# calculator5.net
KiCad netlist of a schematic drawn in EAGLE
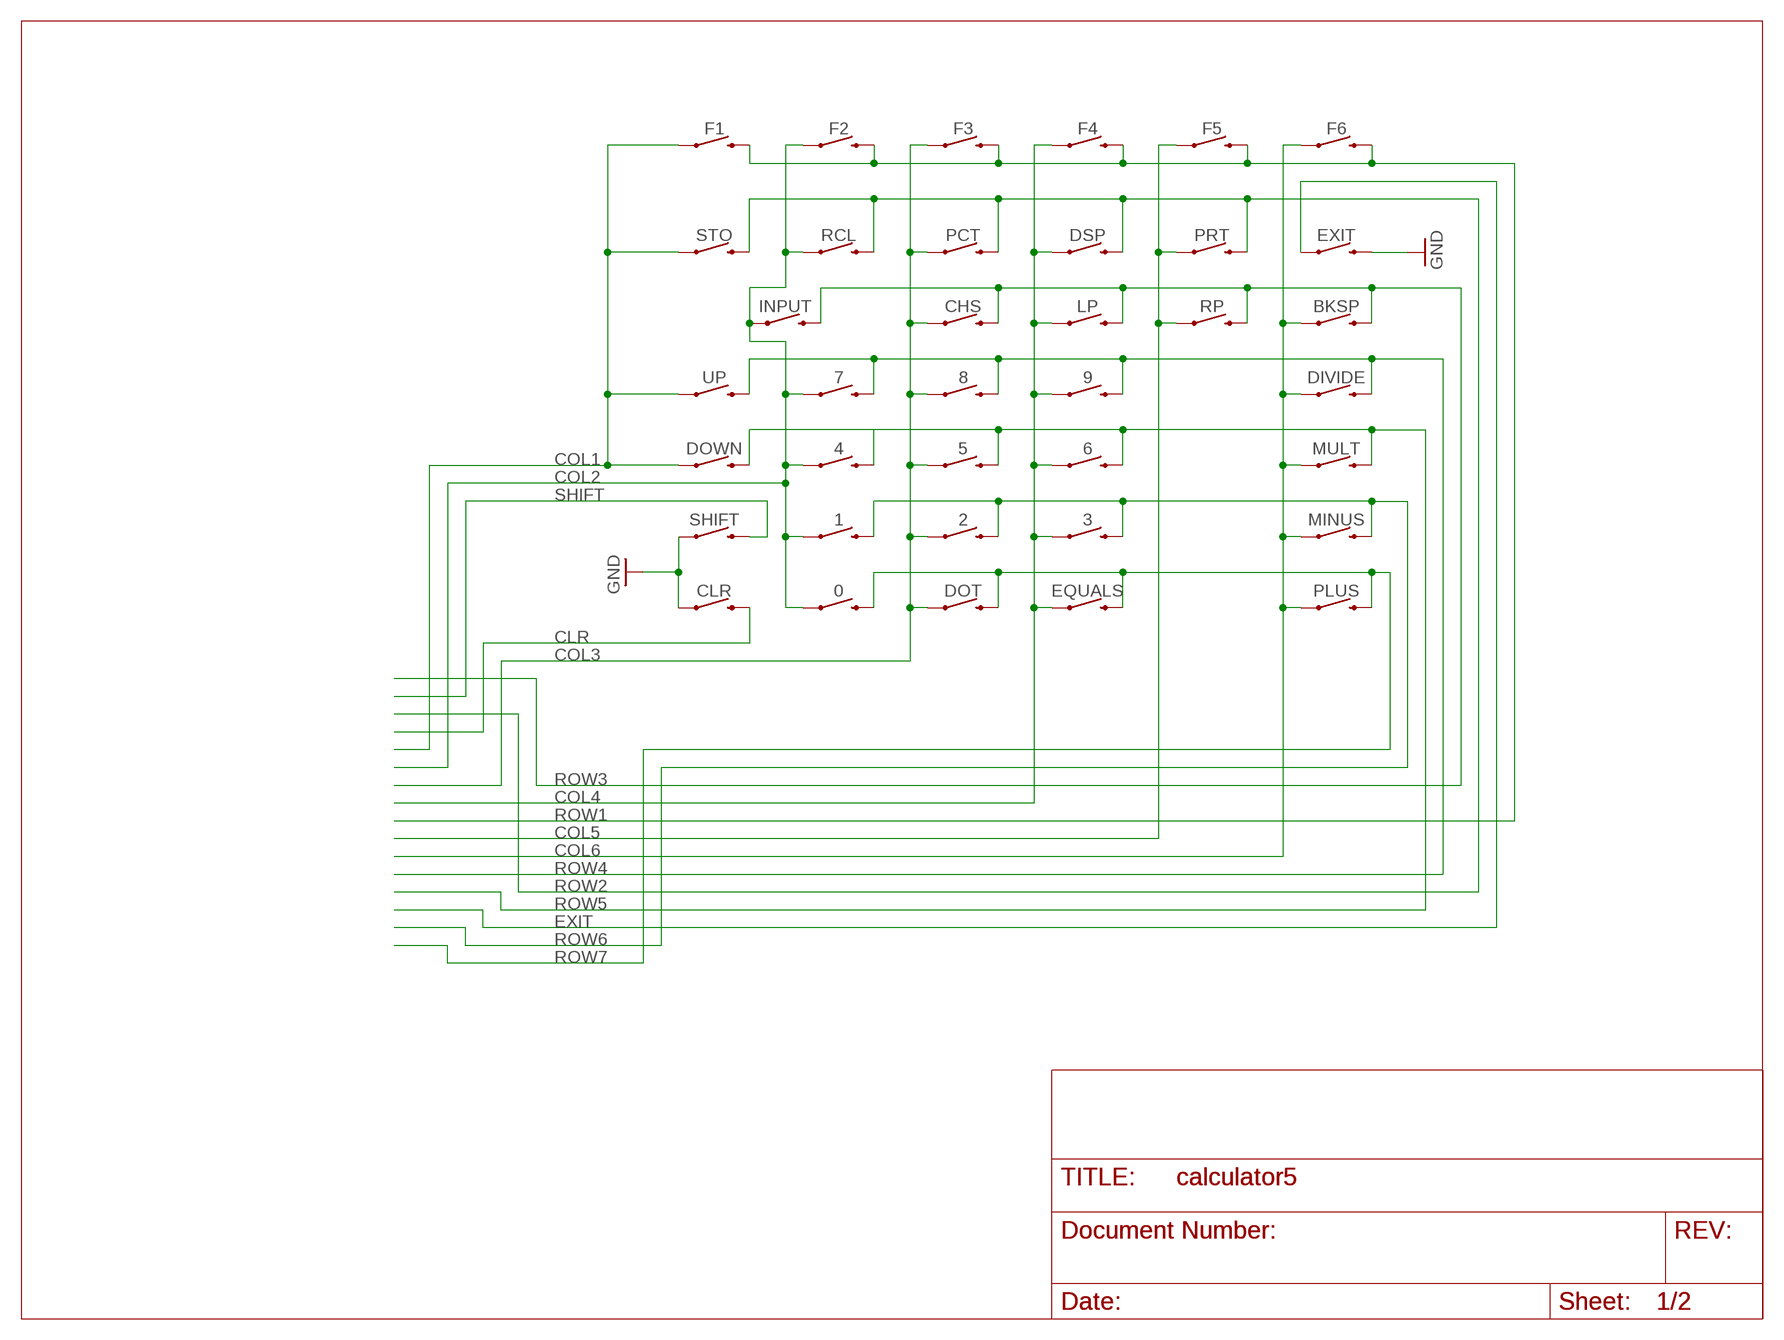
[diagram p0: schematic, sheet 1]
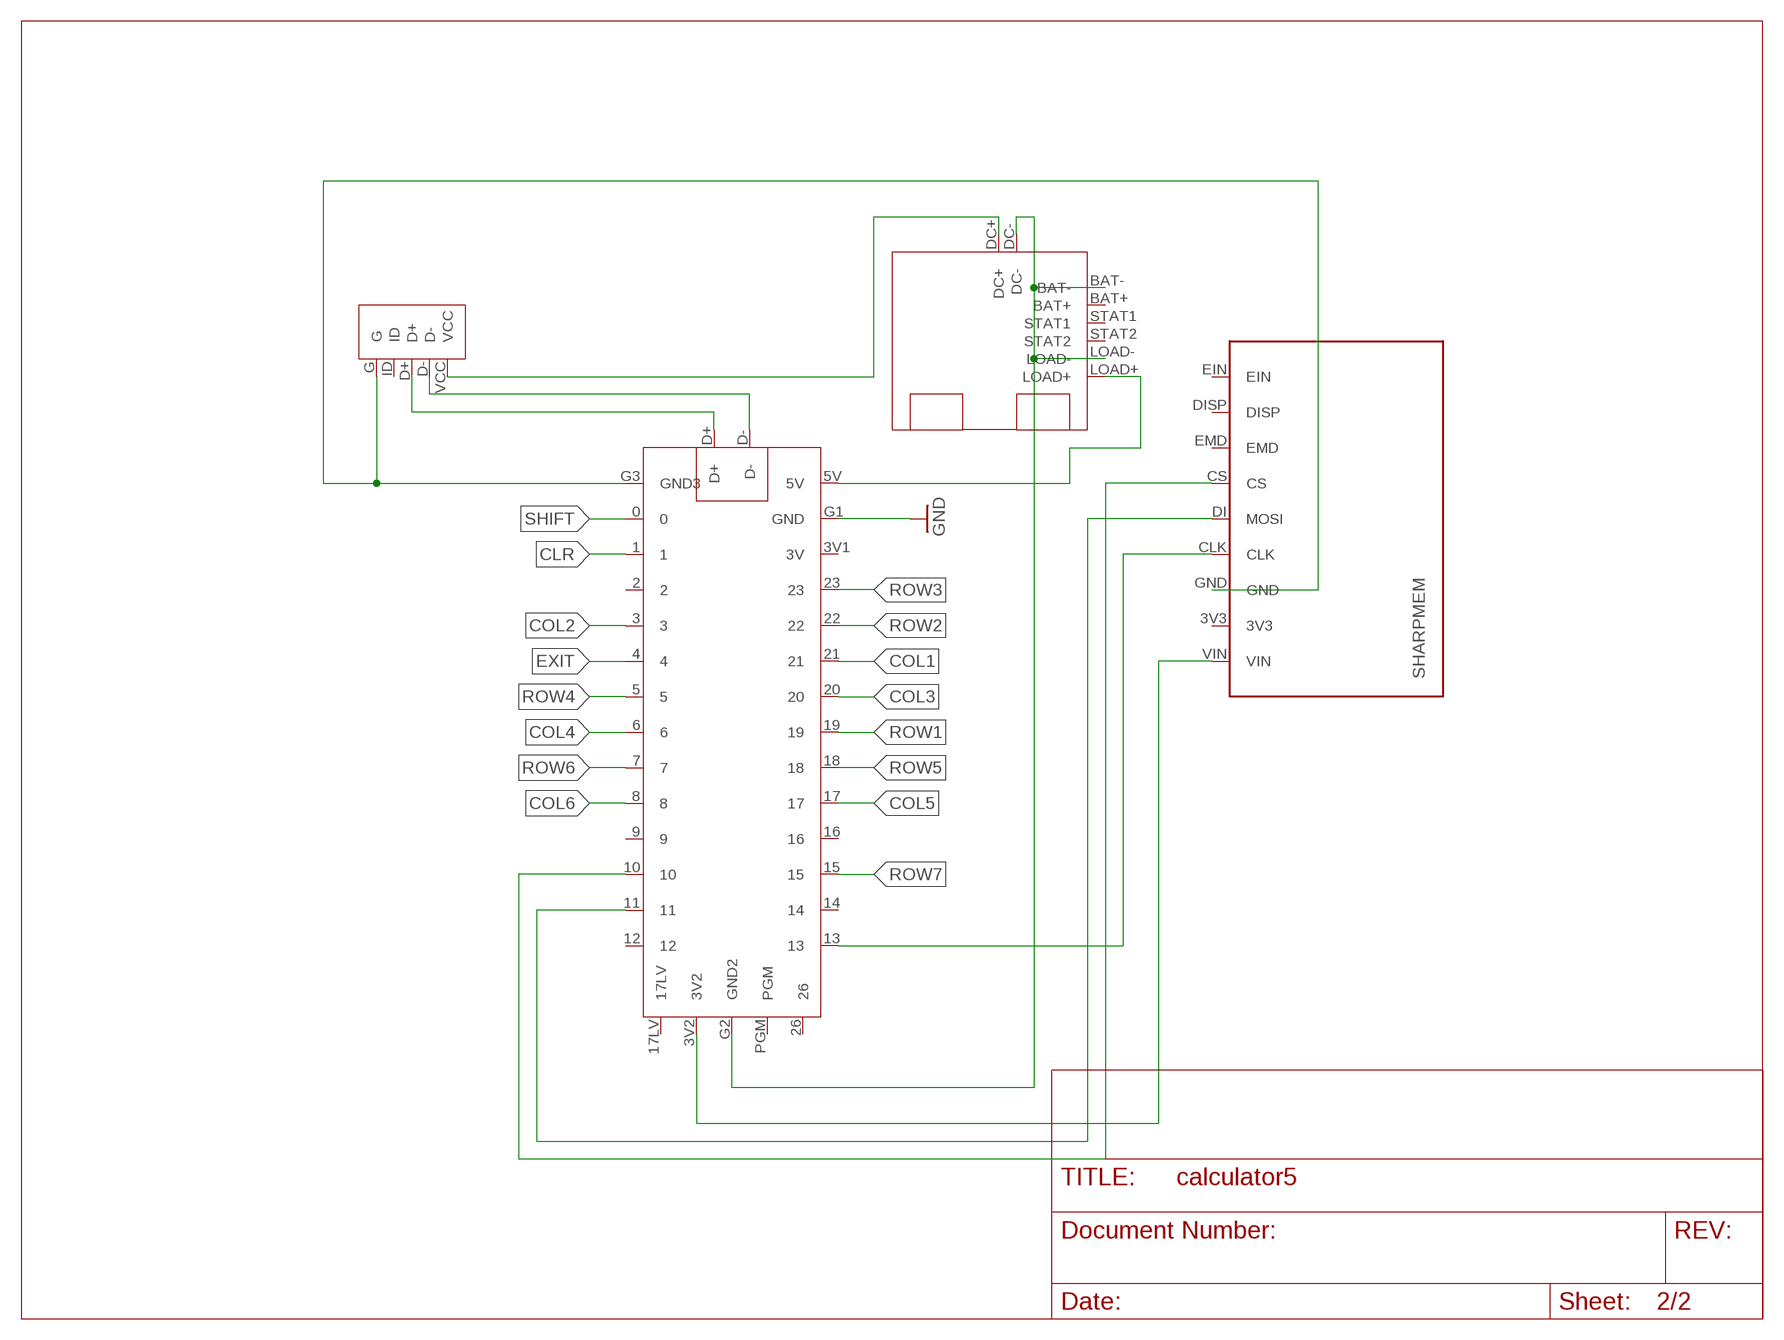
[diagram p1: schematic, sheet 2]

(export (version "E")
  (design (tool "Eeschema 10.0.6"))
  (components
    (comp (ref "0")
      (value "BUTTON")
      (footprint "eagle-import:BUTTON")
      (libsource (lib "eagle-import") (part "BUTTON"))
    )
    (comp (ref "1")
      (value "BUTTON")
      (footprint "eagle-import:BUTTON")
      (libsource (lib "eagle-import") (part "BUTTON"))
    )
    (comp (ref "2")
      (value "BUTTON")
      (footprint "eagle-import:BUTTON")
      (libsource (lib "eagle-import") (part "BUTTON"))
    )
    (comp (ref "3")
      (value "BUTTON")
      (footprint "eagle-import:BUTTON")
      (libsource (lib "eagle-import") (part "BUTTON"))
    )
    (comp (ref "4")
      (value "BUTTON")
      (footprint "eagle-import:BUTTON")
      (libsource (lib "eagle-import") (part "BUTTON"))
    )
    (comp (ref "5")
      (value "BUTTON")
      (footprint "eagle-import:BUTTON")
      (libsource (lib "eagle-import") (part "BUTTON"))
    )
    (comp (ref "6")
      (value "BUTTON")
      (footprint "eagle-import:BUTTON")
      (libsource (lib "eagle-import") (part "BUTTON"))
    )
    (comp (ref "7")
      (value "BUTTON")
      (footprint "eagle-import:BUTTON")
      (libsource (lib "eagle-import") (part "BUTTON"))
    )
    (comp (ref "8")
      (value "BUTTON")
      (footprint "eagle-import:BUTTON")
      (libsource (lib "eagle-import") (part "BUTTON"))
    )
    (comp (ref "9")
      (value "BUTTON")
      (footprint "eagle-import:BUTTON")
      (libsource (lib "eagle-import") (part "BUTTON"))
    )
    (comp (ref "BKSP")
      (value "BUTTON")
      (footprint "eagle-import:BUTTON")
      (libsource (lib "eagle-import") (part "BUTTON"))
    )
    (comp (ref "CHS")
      (value "BUTTON")
      (footprint "eagle-import:BUTTON")
      (libsource (lib "eagle-import") (part "BUTTON"))
    )
    (comp (ref "CLR")
      (value "BUTTON")
      (footprint "eagle-import:BUTTON")
      (libsource (lib "eagle-import") (part "BUTTON"))
    )
    (comp (ref "DIVIDE")
      (value "BUTTON")
      (footprint "eagle-import:BUTTON")
      (libsource (lib "eagle-import") (part "BUTTON"))
    )
    (comp (ref "DOT")
      (value "BUTTON")
      (footprint "eagle-import:BUTTON")
      (libsource (lib "eagle-import") (part "BUTTON"))
    )
    (comp (ref "DOWN")
      (value "BUTTON")
      (footprint "eagle-import:BUTTON")
      (libsource (lib "eagle-import") (part "BUTTON"))
    )
    (comp (ref "DSP")
      (value "BUTTON")
      (footprint "eagle-import:BUTTON")
      (libsource (lib "eagle-import") (part "BUTTON"))
    )
    (comp (ref "EQUALS")
      (value "BUTTON")
      (footprint "eagle-import:BUTTON")
      (libsource (lib "eagle-import") (part "BUTTON"))
    )
    (comp (ref "EXIT")
      (value "BUTTON")
      (footprint "eagle-import:BUTTON")
      (libsource (lib "eagle-import") (part "BUTTON"))
    )
    (comp (ref "F1")
      (value "BUTTON")
      (footprint "eagle-import:BUTTON")
      (libsource (lib "eagle-import") (part "BUTTON"))
    )
    (comp (ref "F2")
      (value "BUTTON")
      (footprint "eagle-import:BUTTON")
      (libsource (lib "eagle-import") (part "BUTTON"))
    )
    (comp (ref "F3")
      (value "BUTTON")
      (footprint "eagle-import:BUTTON")
      (libsource (lib "eagle-import") (part "BUTTON"))
    )
    (comp (ref "F4")
      (value "BUTTON")
      (footprint "eagle-import:BUTTON")
      (libsource (lib "eagle-import") (part "BUTTON"))
    )
    (comp (ref "F5")
      (value "BUTTON")
      (footprint "eagle-import:BUTTON")
      (libsource (lib "eagle-import") (part "BUTTON"))
    )
    (comp (ref "F6")
      (value "BUTTON")
      (footprint "eagle-import:BUTTON")
      (libsource (lib "eagle-import") (part "BUTTON"))
    )
    (comp (ref "INPUT")
      (value "BUTTON")
      (footprint "eagle-import:BUTTON")
      (libsource (lib "eagle-import") (part "BUTTON"))
    )
    (comp (ref "LP")
      (value "BUTTON")
      (footprint "eagle-import:BUTTON")
      (libsource (lib "eagle-import") (part "BUTTON"))
    )
    (comp (ref "MINUS")
      (value "BUTTON")
      (footprint "eagle-import:BUTTON")
      (libsource (lib "eagle-import") (part "BUTTON"))
    )
    (comp (ref "MULT")
      (value "BUTTON")
      (footprint "eagle-import:BUTTON")
      (libsource (lib "eagle-import") (part "BUTTON"))
    )
    (comp (ref "PCT")
      (value "BUTTON")
      (footprint "eagle-import:BUTTON")
      (libsource (lib "eagle-import") (part "BUTTON"))
    )
    (comp (ref "PLUS")
      (value "BUTTON")
      (footprint "eagle-import:BUTTON")
      (libsource (lib "eagle-import") (part "BUTTON"))
    )
    (comp (ref "PRT")
      (value "BUTTON")
      (footprint "eagle-import:BUTTON")
      (libsource (lib "eagle-import") (part "BUTTON"))
    )
    (comp (ref "RCL")
      (value "BUTTON")
      (footprint "eagle-import:BUTTON")
      (libsource (lib "eagle-import") (part "BUTTON"))
    )
    (comp (ref "RP")
      (value "BUTTON")
      (footprint "eagle-import:BUTTON")
      (libsource (lib "eagle-import") (part "BUTTON"))
    )
    (comp (ref "SHIFT")
      (value "BUTTON")
      (footprint "eagle-import:BUTTON")
      (libsource (lib "eagle-import") (part "BUTTON"))
    )
    (comp (ref "STO")
      (value "BUTTON")
      (footprint "eagle-import:BUTTON")
      (libsource (lib "eagle-import") (part "BUTTON"))
    )
    (comp (ref "UP")
      (value "BUTTON")
      (footprint "eagle-import:BUTTON")
      (libsource (lib "eagle-import") (part "BUTTON"))
    )
    (comp (ref "SHARPMEM")
      (value "SHARPMEM")
      (footprint "eagle-import:SHARPMEM")
      (libsource (lib "eagle-import") (part "SHARPMEM"))
    )
    (comp (ref "U$1")
      (value "TEENSY_LC")
      (footprint "eagle-import:TEENSY_LC")
      (libsource (lib "eagle-import") (part "TEENSY_LC"))
    )
    (comp (ref "U$2")
      (value "USB")
      (footprint "eagle-import:USB")
      (libsource (lib "eagle-import") (part "USB"))
    )
    (comp (ref "U$3")
      (value "LIPO_CHARGER")
      (footprint "eagle-import:LIPO_CHARGER")
      (libsource (lib "eagle-import") (part "LIPO_CHARGER"))
    )
  )
  (nets
    (net (code "1") (name "CLR") (class "Default")
      (node (ref "CLR") (pin "3") (pinfunction "2_3") (pintype "passive"))
      (node (ref "U$1") (pin "1") (pinfunction "1_1") (pintype "bidirectional"))
    )
    (net (code "2") (name "COL1") (class "Default")
      (node (ref "DOWN") (pin "1") (pinfunction "1_1") (pintype "passive"))
      (node (ref "F1") (pin "1") (pinfunction "1_1") (pintype "passive"))
      (node (ref "STO") (pin "1") (pinfunction "1_1") (pintype "passive"))
      (node (ref "U$1") (pin "21") (pinfunction "21_21") (pintype "bidirectional"))
      (node (ref "UP") (pin "1") (pinfunction "1_1") (pintype "passive"))
    )
    (net (code "3") (name "COL2") (class "Default")
      (node (ref "0") (pin "1") (pinfunction "1_1") (pintype "passive"))
      (node (ref "1") (pin "1") (pinfunction "1_1") (pintype "passive"))
      (node (ref "4") (pin "1") (pinfunction "1_1") (pintype "passive"))
      (node (ref "7") (pin "1") (pinfunction "1_1") (pintype "passive"))
      (node (ref "F2") (pin "1") (pinfunction "1_1") (pintype "passive"))
      (node (ref "INPUT") (pin "1") (pinfunction "1_1") (pintype "passive"))
      (node (ref "RCL") (pin "1") (pinfunction "1_1") (pintype "passive"))
      (node (ref "U$1") (pin "3") (pinfunction "3_3") (pintype "bidirectional"))
    )
    (net (code "4") (name "COL3") (class "Default")
      (node (ref "2") (pin "1") (pinfunction "1_1") (pintype "passive"))
      (node (ref "5") (pin "1") (pinfunction "1_1") (pintype "passive"))
      (node (ref "8") (pin "1") (pinfunction "1_1") (pintype "passive"))
      (node (ref "CHS") (pin "1") (pinfunction "1_1") (pintype "passive"))
      (node (ref "DOT") (pin "1") (pinfunction "1_1") (pintype "passive"))
      (node (ref "F3") (pin "1") (pinfunction "1_1") (pintype "passive"))
      (node (ref "PCT") (pin "1") (pinfunction "1_1") (pintype "passive"))
      (node (ref "U$1") (pin "20") (pinfunction "20_20") (pintype "bidirectional"))
    )
    (net (code "5") (name "COL4") (class "Default")
      (node (ref "3") (pin "1") (pinfunction "1_1") (pintype "passive"))
      (node (ref "6") (pin "1") (pinfunction "1_1") (pintype "passive"))
      (node (ref "9") (pin "1") (pinfunction "1_1") (pintype "passive"))
      (node (ref "DSP") (pin "1") (pinfunction "1_1") (pintype "passive"))
      (node (ref "EQUALS") (pin "1") (pinfunction "1_1") (pintype "passive"))
      (node (ref "F4") (pin "1") (pinfunction "1_1") (pintype "passive"))
      (node (ref "LP") (pin "1") (pinfunction "1_1") (pintype "passive"))
      (node (ref "U$1") (pin "6") (pinfunction "6_6") (pintype "bidirectional"))
    )
    (net (code "6") (name "COL5") (class "Default")
      (node (ref "F5") (pin "1") (pinfunction "1_1") (pintype "passive"))
      (node (ref "PRT") (pin "1") (pinfunction "1_1") (pintype "passive"))
      (node (ref "RP") (pin "1") (pinfunction "1_1") (pintype "passive"))
      (node (ref "U$1") (pin "17") (pinfunction "17_17") (pintype "bidirectional"))
    )
    (net (code "7") (name "COL6") (class "Default")
      (node (ref "BKSP") (pin "1") (pinfunction "1_1") (pintype "passive"))
      (node (ref "DIVIDE") (pin "1") (pinfunction "1_1") (pintype "passive"))
      (node (ref "F6") (pin "1") (pinfunction "1_1") (pintype "passive"))
      (node (ref "MINUS") (pin "1") (pinfunction "1_1") (pintype "passive"))
      (node (ref "MULT") (pin "1") (pinfunction "1_1") (pintype "passive"))
      (node (ref "PLUS") (pin "1") (pinfunction "1_1") (pintype "passive"))
      (node (ref "U$1") (pin "8") (pinfunction "8_8") (pintype "bidirectional"))
    )
    (net (code "8") (name "EXIT") (class "Default")
      (node (ref "EXIT") (pin "1") (pinfunction "1_1") (pintype "passive"))
      (node (ref "U$1") (pin "4") (pinfunction "4_4") (pintype "bidirectional"))
    )
    (net (code "9") (name "GND") (class "Default")
      (node (ref "CLR") (pin "1") (pinfunction "1_1") (pintype "passive"))
      (node (ref "EXIT") (pin "3") (pinfunction "2_3") (pintype "passive"))
      (node (ref "SHIFT") (pin "1") (pinfunction "1_1") (pintype "passive"))
      (node (ref "U$1") (pin "G1") (pinfunction "GND_G1") (pintype "bidirectional"))
    )
    (net (code "10") (name "Net-(SHARPMEM-MOSI)") (class "Default")
      (node (ref "SHARPMEM") (pin "DI") (pinfunction "MOSI_DI") (pintype "bidirectional"))
      (node (ref "U$1") (pin "11") (pinfunction "11_11") (pintype "bidirectional"))
    )
    (net (code "11") (name "Net-(SHARPMEM-PadCLK)") (class "Default")
      (node (ref "SHARPMEM") (pin "CLK") (pinfunction "CLK_CLK") (pintype "bidirectional"))
      (node (ref "U$1") (pin "13") (pinfunction "13_13") (pintype "bidirectional"))
    )
    (net (code "12") (name "Net-(SHARPMEM-PadCS)") (class "Default")
      (node (ref "SHARPMEM") (pin "CS") (pinfunction "CS_CS") (pintype "bidirectional"))
      (node (ref "U$1") (pin "10") (pinfunction "10_10") (pintype "bidirectional"))
    )
    (net (code "13") (name "Net-(SHARPMEM-PadVIN)") (class "Default")
      (node (ref "SHARPMEM") (pin "VIN") (pinfunction "VIN_VIN") (pintype "bidirectional"))
      (node (ref "U$1") (pin "3V2") (pinfunction "3V2_3V2") (pintype "bidirectional"))
    )
    (net (code "14") (name "Net-(U$1-GND2)") (class "Default")
      (node (ref "U$1") (pin "G2") (pinfunction "GND2_G2") (pintype "bidirectional"))
      (node (ref "U$3") (pin "BAT-") (pinfunction "BAT-_BAT-") (pintype "bidirectional"))
      (node (ref "U$3") (pin "DC-") (pinfunction "DC-_DC-") (pintype "bidirectional"))
      (node (ref "U$3") (pin "LOAD-") (pinfunction "LOAD-_LOAD-") (pintype "bidirectional"))
    )
    (net (code "15") (name "Net-(U$1-GND3)") (class "Default")
      (node (ref "SHARPMEM") (pin "GND") (pinfunction "GND_GND") (pintype "bidirectional"))
      (node (ref "U$1") (pin "G3") (pinfunction "GND3_G3") (pintype "bidirectional"))
      (node (ref "U$2") (pin "G") (pinfunction "G_G") (pintype "bidirectional"))
    )
    (net (code "16") (name "Net-(U$1-Pad5V)") (class "Default")
      (node (ref "U$1") (pin "5V") (pinfunction "5V_5V") (pintype "bidirectional"))
      (node (ref "U$3") (pin "LOAD+") (pinfunction "LOAD+_LOAD+") (pintype "bidirectional"))
    )
    (net (code "17") (name "Net-(U$1-PadD+)") (class "Default")
      (node (ref "U$1") (pin "D+") (pinfunction "D+_D+") (pintype "bidirectional"))
      (node (ref "U$2") (pin "D+") (pinfunction "D+_D+") (pintype "bidirectional"))
    )
    (net (code "18") (name "Net-(U$1-PadD-)") (class "Default")
      (node (ref "U$1") (pin "D-") (pinfunction "D-_D-") (pintype "bidirectional"))
      (node (ref "U$2") (pin "D-") (pinfunction "D-_D-") (pintype "bidirectional"))
    )
    (net (code "19") (name "Net-(U$2-PadVCC)") (class "Default")
      (node (ref "U$2") (pin "VCC") (pinfunction "VCC_VCC") (pintype "bidirectional"))
      (node (ref "U$3") (pin "DC+") (pinfunction "DC+_DC+") (pintype "bidirectional"))
    )
    (net (code "20") (name "ROW1") (class "Default")
      (node (ref "F1") (pin "3") (pinfunction "2_3") (pintype "passive"))
      (node (ref "F2") (pin "3") (pinfunction "2_3") (pintype "passive"))
      (node (ref "F3") (pin "3") (pinfunction "2_3") (pintype "passive"))
      (node (ref "F4") (pin "3") (pinfunction "2_3") (pintype "passive"))
      (node (ref "F5") (pin "3") (pinfunction "2_3") (pintype "passive"))
      (node (ref "F6") (pin "3") (pinfunction "2_3") (pintype "passive"))
      (node (ref "U$1") (pin "19") (pinfunction "19_19") (pintype "bidirectional"))
    )
    (net (code "21") (name "ROW2") (class "Default")
      (node (ref "DSP") (pin "3") (pinfunction "2_3") (pintype "passive"))
      (node (ref "PCT") (pin "3") (pinfunction "2_3") (pintype "passive"))
      (node (ref "PRT") (pin "3") (pinfunction "2_3") (pintype "passive"))
      (node (ref "RCL") (pin "3") (pinfunction "2_3") (pintype "passive"))
      (node (ref "STO") (pin "3") (pinfunction "2_3") (pintype "passive"))
      (node (ref "U$1") (pin "22") (pinfunction "22_22") (pintype "bidirectional"))
    )
    (net (code "22") (name "ROW3") (class "Default")
      (node (ref "BKSP") (pin "3") (pinfunction "2_3") (pintype "passive"))
      (node (ref "CHS") (pin "3") (pinfunction "2_3") (pintype "passive"))
      (node (ref "INPUT") (pin "3") (pinfunction "2_3") (pintype "passive"))
      (node (ref "LP") (pin "3") (pinfunction "2_3") (pintype "passive"))
      (node (ref "RP") (pin "3") (pinfunction "2_3") (pintype "passive"))
      (node (ref "U$1") (pin "23") (pinfunction "23_23") (pintype "bidirectional"))
    )
    (net (code "23") (name "ROW4") (class "Default")
      (node (ref "7") (pin "3") (pinfunction "2_3") (pintype "passive"))
      (node (ref "8") (pin "3") (pinfunction "2_3") (pintype "passive"))
      (node (ref "9") (pin "3") (pinfunction "2_3") (pintype "passive"))
      (node (ref "DIVIDE") (pin "3") (pinfunction "2_3") (pintype "passive"))
      (node (ref "U$1") (pin "5") (pinfunction "5_5") (pintype "bidirectional"))
      (node (ref "UP") (pin "3") (pinfunction "2_3") (pintype "passive"))
    )
    (net (code "24") (name "ROW5") (class "Default")
      (node (ref "4") (pin "3") (pinfunction "2_3") (pintype "passive"))
      (node (ref "5") (pin "3") (pinfunction "2_3") (pintype "passive"))
      (node (ref "6") (pin "3") (pinfunction "2_3") (pintype "passive"))
      (node (ref "DOWN") (pin "3") (pinfunction "2_3") (pintype "passive"))
      (node (ref "MULT") (pin "3") (pinfunction "2_3") (pintype "passive"))
      (node (ref "U$1") (pin "18") (pinfunction "18_18") (pintype "bidirectional"))
    )
    (net (code "25") (name "ROW6") (class "Default")
      (node (ref "1") (pin "3") (pinfunction "2_3") (pintype "passive"))
      (node (ref "2") (pin "3") (pinfunction "2_3") (pintype "passive"))
      (node (ref "3") (pin "3") (pinfunction "2_3") (pintype "passive"))
      (node (ref "MINUS") (pin "3") (pinfunction "2_3") (pintype "passive"))
      (node (ref "U$1") (pin "7") (pinfunction "7_7") (pintype "bidirectional"))
    )
    (net (code "26") (name "ROW7") (class "Default")
      (node (ref "0") (pin "3") (pinfunction "2_3") (pintype "passive"))
      (node (ref "DOT") (pin "3") (pinfunction "2_3") (pintype "passive"))
      (node (ref "EQUALS") (pin "3") (pinfunction "2_3") (pintype "passive"))
      (node (ref "PLUS") (pin "3") (pinfunction "2_3") (pintype "passive"))
      (node (ref "U$1") (pin "15") (pinfunction "15_15") (pintype "bidirectional"))
    )
    (net (code "27") (name "SHIFT") (class "Default")
      (node (ref "SHIFT") (pin "3") (pinfunction "2_3") (pintype "passive"))
      (node (ref "U$1") (pin "0") (pinfunction "0_0") (pintype "bidirectional"))
    )
    (net (code "28") (name "unconnected-(SHARPMEM-Pad3V3)") (class "Default")
      (node (ref "SHARPMEM") (pin "3V3") (pinfunction "3V3_3V3") (pintype "bidirectional"))
    )
    (net (code "29") (name "unconnected-(SHARPMEM-PadDISP)") (class "Default")
      (node (ref "SHARPMEM") (pin "DISP") (pinfunction "DISP_DISP") (pintype "bidirectional"))
    )
    (net (code "30") (name "unconnected-(SHARPMEM-PadEIN)") (class "Default")
      (node (ref "SHARPMEM") (pin "EIN") (pinfunction "EIN_EIN") (pintype "bidirectional"))
    )
    (net (code "31") (name "unconnected-(SHARPMEM-PadEMD)") (class "Default")
      (node (ref "SHARPMEM") (pin "EMD") (pinfunction "EMD_EMD") (pintype "bidirectional"))
    )
    (net (code "32") (name "unconnected-(U$1-3V-Pad3V1)") (class "Default")
      (node (ref "U$1") (pin "3V1") (pinfunction "3V_3V1") (pintype "bidirectional"))
    )
    (net (code "33") (name "unconnected-(U$1-Pad2)") (class "Default")
      (node (ref "U$1") (pin "2") (pinfunction "2_2") (pintype "bidirectional"))
    )
    (net (code "34") (name "unconnected-(U$1-Pad9)") (class "Default")
      (node (ref "U$1") (pin "9") (pinfunction "9_9") (pintype "bidirectional"))
    )
    (net (code "35") (name "unconnected-(U$1-Pad12)") (class "Default")
      (node (ref "U$1") (pin "12") (pinfunction "12_12") (pintype "bidirectional"))
    )
    (net (code "36") (name "unconnected-(U$1-Pad14)") (class "Default")
      (node (ref "U$1") (pin "14") (pinfunction "14_14") (pintype "bidirectional"))
    )
    (net (code "37") (name "unconnected-(U$1-Pad16)") (class "Default")
      (node (ref "U$1") (pin "16") (pinfunction "16_16") (pintype "bidirectional"))
    )
    (net (code "38") (name "unconnected-(U$1-Pad17LV)") (class "Default")
      (node (ref "U$1") (pin "17LV") (pinfunction "17LV_17LV") (pintype "bidirectional"))
    )
    (net (code "39") (name "unconnected-(U$1-Pad26)") (class "Default")
      (node (ref "U$1") (pin "26") (pinfunction "26_26") (pintype "bidirectional"))
    )
    (net (code "40") (name "unconnected-(U$1-PadPGM)") (class "Default")
      (node (ref "U$1") (pin "PGM") (pinfunction "PGM_PGM") (pintype "bidirectional"))
    )
    (net (code "41") (name "unconnected-(U$2-PadID)") (class "Default")
      (node (ref "U$2") (pin "ID") (pinfunction "ID_ID") (pintype "bidirectional"))
    )
    (net (code "42") (name "unconnected-(U$3-PadBAT+)") (class "Default")
      (node (ref "U$3") (pin "BAT+") (pinfunction "BAT+_BAT+") (pintype "bidirectional"))
    )
    (net (code "43") (name "unconnected-(U$3-PadSTAT1)") (class "Default")
      (node (ref "U$3") (pin "STAT1") (pinfunction "STAT1_STAT1") (pintype "bidirectional"))
    )
    (net (code "44") (name "unconnected-(U$3-PadSTAT2)") (class "Default")
      (node (ref "U$3") (pin "STAT2") (pinfunction "STAT2_STAT2") (pintype "bidirectional"))
    )
  )
)
